# BB-Powersupply_KNX-Connection.net
KiCad netlist of a schematic drawn in EAGLE
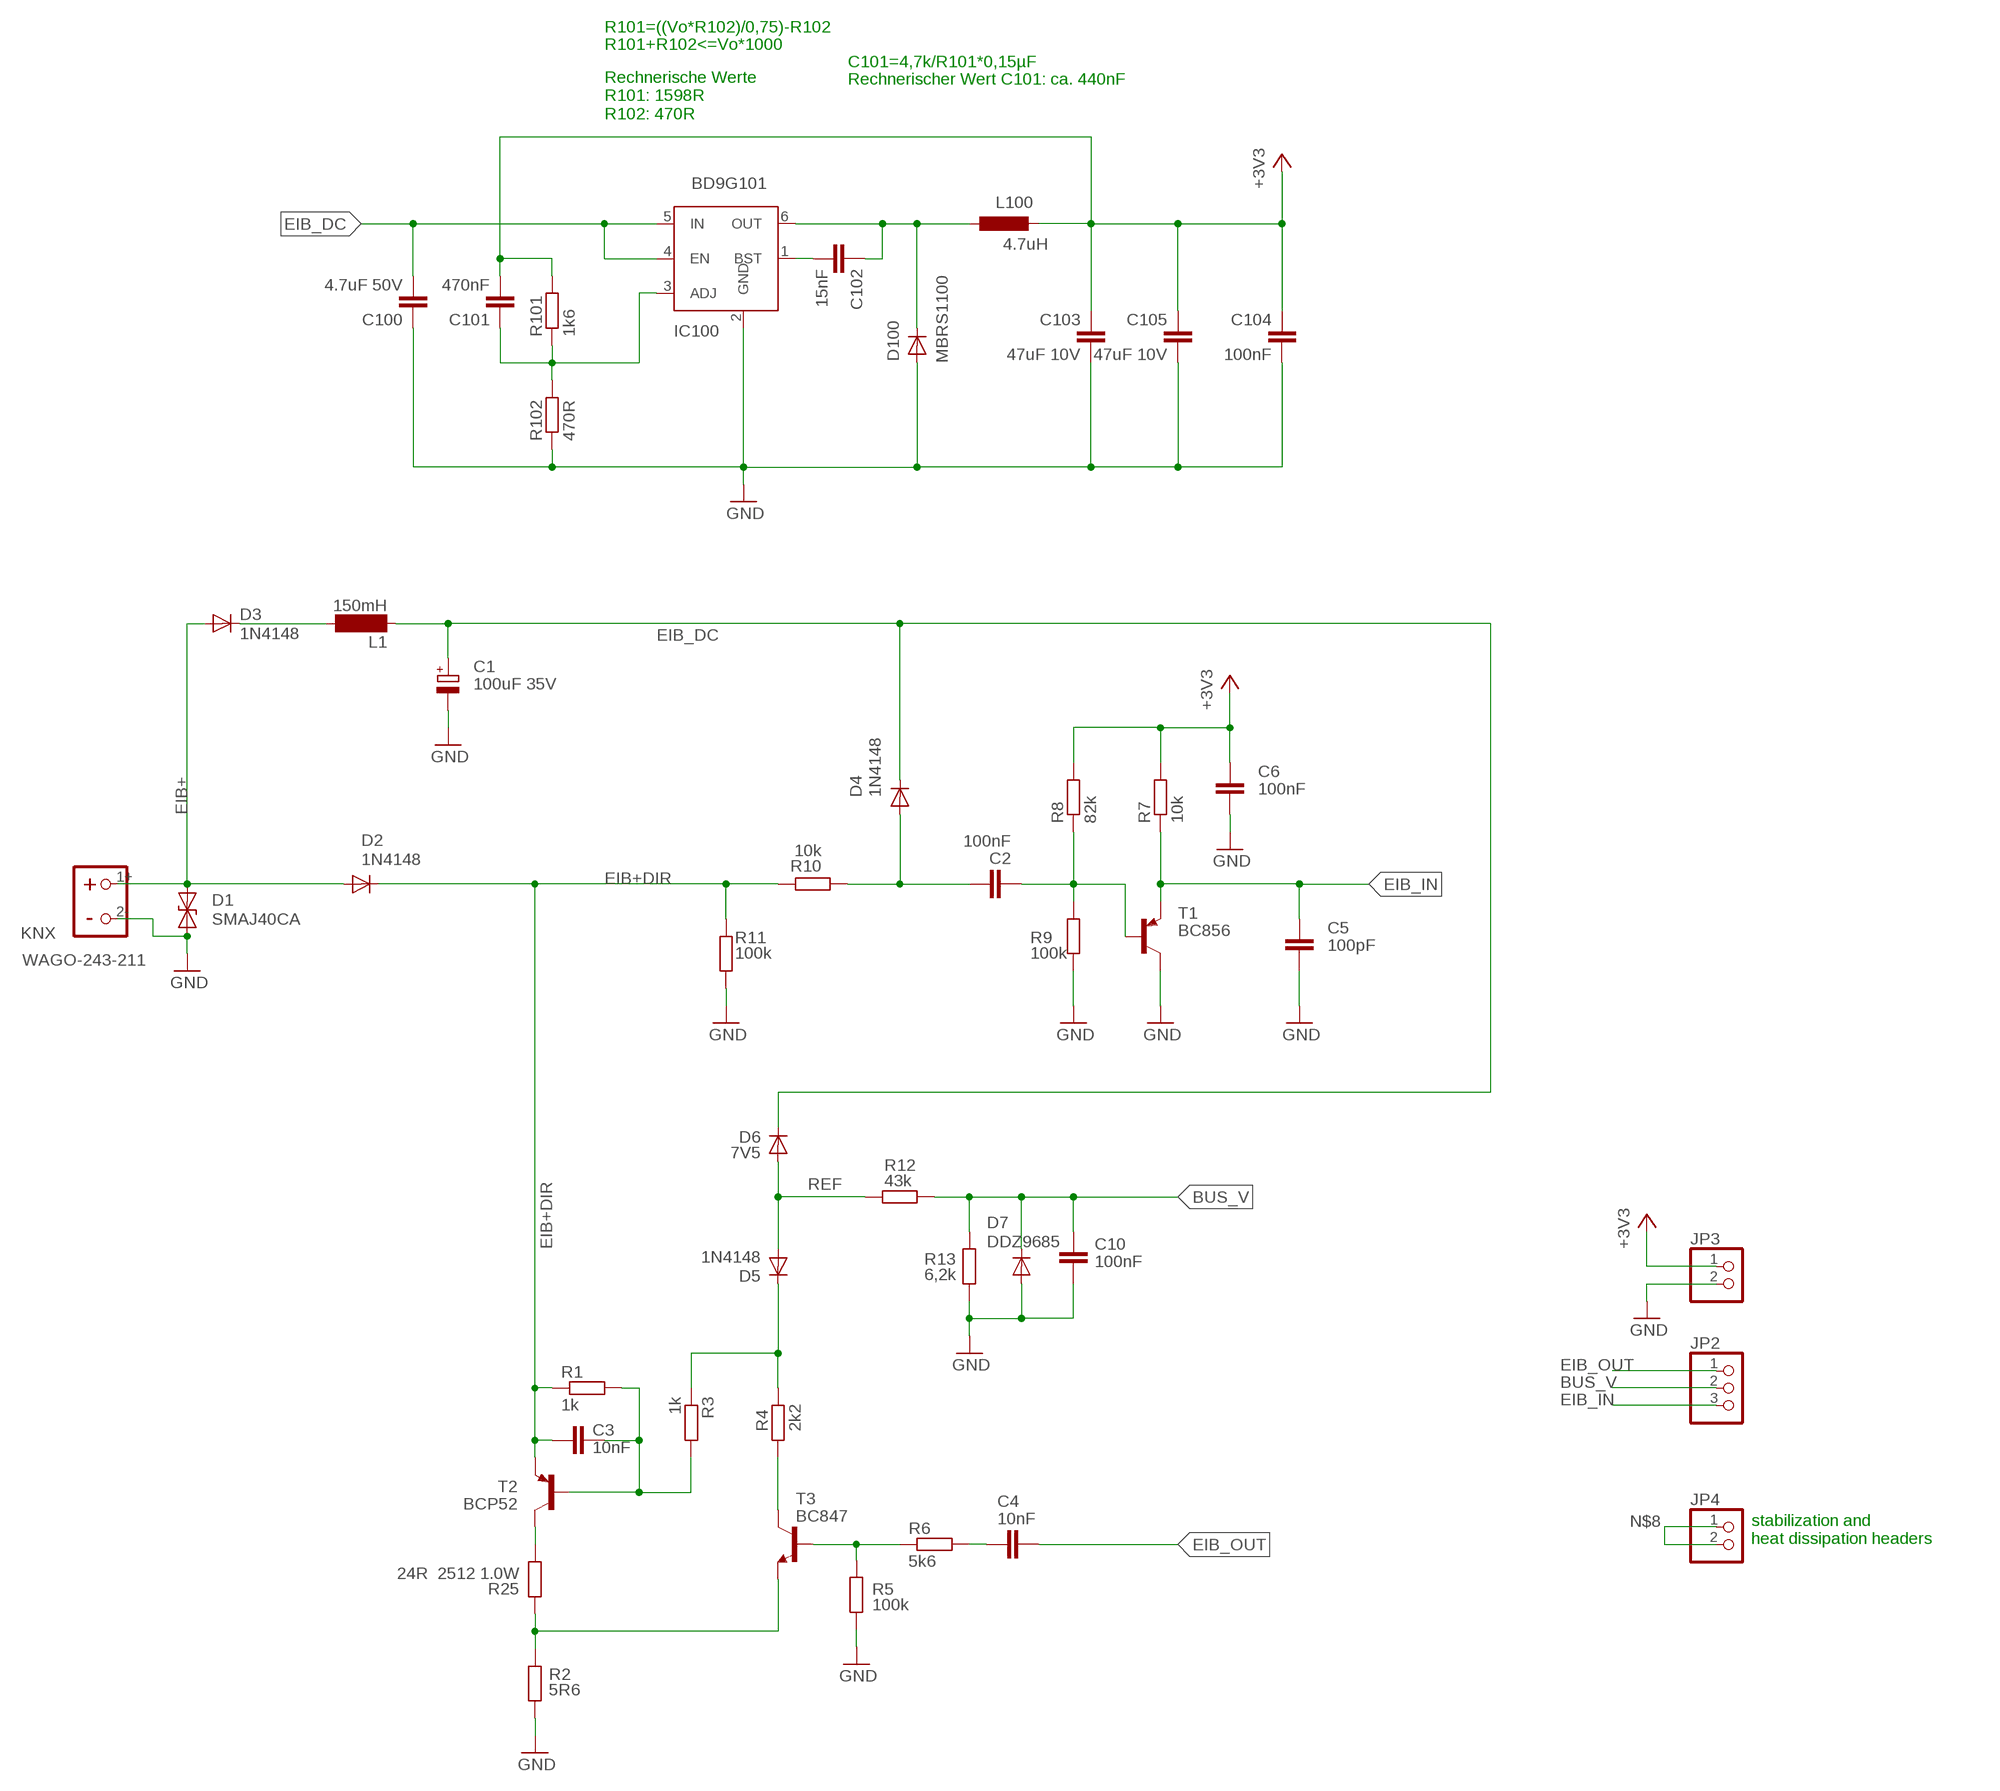
[diagram p0: schematic, sheet 1]

(export (version "E")
  (design (tool "Eeschema 10.0.6"))
  (components
    (comp (ref "C1")
      (value "100uF 35V")
      (footprint "eagle-import:SANYO-OSCON_SMD_C6")
      (libsource (lib "eagle-import") (part "CPOL-EUSANYO_SMD_C6"))
    )
    (comp (ref "C2")
      (value "100nF")
      (footprint "eagle-import:C0805")
      (libsource (lib "eagle-import") (part "C-EUC0805"))
    )
    (comp (ref "C3")
      (value "10nF")
      (footprint "eagle-import:C0805")
      (libsource (lib "eagle-import") (part "C-EUC0805"))
    )
    (comp (ref "C4")
      (value "10nF")
      (footprint "eagle-import:C0805")
      (libsource (lib "eagle-import") (part "C-EUC0805"))
    )
    (comp (ref "C5")
      (value "100pF")
      (footprint "eagle-import:C0805")
      (libsource (lib "eagle-import") (part "C-EUC0805"))
    )
    (comp (ref "C6")
      (value "100nF")
      (footprint "eagle-import:C0805")
      (libsource (lib "eagle-import") (part "C-EUC0805"))
    )
    (comp (ref "C10")
      (value "100nF")
      (footprint "eagle-import:C0805")
      (libsource (lib "eagle-import") (part "C-EUC0805"))
    )
    (comp (ref "C100")
      (value "4.7uF 50V")
      (footprint "eagle-import:C0805")
      (libsource (lib "eagle-import") (part "C-EUC0805"))
    )
    (comp (ref "C101")
      (value "470nF")
      (footprint "eagle-import:C0805")
      (libsource (lib "eagle-import") (part "C-EUC0805"))
    )
    (comp (ref "C102")
      (value "15nF")
      (footprint "eagle-import:C0805")
      (libsource (lib "eagle-import") (part "C-EUC0805"))
    )
    (comp (ref "C103")
      (value "47uF 10V")
      (footprint "eagle-import:C0805")
      (libsource (lib "eagle-import") (part "C-EUC0805"))
    )
    (comp (ref "C104")
      (value "100nF")
      (footprint "eagle-import:C0805")
      (libsource (lib "eagle-import") (part "C-EUC0805"))
    )
    (comp (ref "C105")
      (value "47uF 10V")
      (footprint "eagle-import:C0805")
      (libsource (lib "eagle-import") (part "C-EUC0805"))
    )
    (comp (ref "D1")
      (value "SMAJ40CA")
      (footprint "eagle-import:DO214AC")
      (fields (field (name "MF") "Littelfuse"))
      (libsource (lib "eagle-import") (part "SMAJCA40"))
    )
    (comp (ref "D2")
      (value "1N4148")
      (footprint "eagle-import:SOD-123")
      (libsource (lib "eagle-import") (part "DIODESOD-123"))
    )
    (comp (ref "D3")
      (value "1N4148")
      (footprint "eagle-import:SOD-123")
      (libsource (lib "eagle-import") (part "DIODESOD-123"))
    )
    (comp (ref "D4")
      (value "1N4148")
      (footprint "eagle-import:SOD-123")
      (libsource (lib "eagle-import") (part "DIODESOD-123"))
    )
    (comp (ref "D5")
      (value "1N4148")
      (footprint "eagle-import:SOD-123")
      (libsource (lib "eagle-import") (part "DIODESOD-123"))
    )
    (comp (ref "D6")
      (value "7V5")
      (footprint "eagle-import:SOD-123")
      (libsource (lib "eagle-import") (part "DIODESOD-123"))
    )
    (comp (ref "D7")
      (value "DDZ9685")
      (footprint "eagle-import:SOD-123")
      (libsource (lib "eagle-import") (part "DIODESOD-123"))
    )
    (comp (ref "D100")
      (value "MBRS1100")
      (footprint "eagle-import:SOD-123")
      (libsource (lib "eagle-import") (part "DIODESOD-123"))
    )
    (comp (ref "IC100")
      (value "BD9G101")
      (footprint "eagle-import:SOT23-6")
      (libsource (lib "eagle-import") (part "BD9G101GBD9G101G-SOT23-6"))
    )
    (comp (ref "JP2")
      (value "PINHD-1X3")
      (footprint "eagle-import:1X03")
      (libsource (lib "eagle-import") (part "PINHD-1X3"))
    )
    (comp (ref "JP3")
      (value "PINHD-1X2")
      (footprint "eagle-import:1X02")
      (libsource (lib "eagle-import") (part "PINHD-1X2"))
    )
    (comp (ref "JP4")
      (value "PINHD-1X2")
      (footprint "eagle-import:1X02")
      (libsource (lib "eagle-import") (part "PINHD-1X2"))
    )
    (comp (ref "KNX")
      (value "WAGO-243-211")
      (footprint "eagle-import:WAGO-243-211")
      (libsource (lib "eagle-import") (part "WAGO-243-211"))
    )
    (comp (ref "L1")
      (value "150mH")
      (footprint "eagle-import:BS11")
      (fields (field (name "SPICEPREFIX") "L"))
      (libsource (lib "eagle-import") (part "BS11"))
    )
    (comp (ref "L100")
      (value "4.7uH")
      (footprint "eagle-import:L4532P")
      (libsource (lib "eagle-import") (part "L-EUL4532P"))
    )
    (comp (ref "R1")
      (value "1k")
      (footprint "eagle-import:R0805")
      (libsource (lib "eagle-import") (part "R-EU_R0805"))
    )
    (comp (ref "R2")
      (value "5R6")
      (footprint "eagle-import:R0805")
      (libsource (lib "eagle-import") (part "R-EU_R0805"))
    )
    (comp (ref "R3")
      (value "1k")
      (footprint "eagle-import:R0805")
      (libsource (lib "eagle-import") (part "R-EU_R0805"))
    )
    (comp (ref "R4")
      (value "2k2")
      (footprint "eagle-import:R0805")
      (libsource (lib "eagle-import") (part "R-EU_R0805"))
    )
    (comp (ref "R5")
      (value "100k")
      (footprint "eagle-import:R0805")
      (libsource (lib "eagle-import") (part "R-EU_R0805"))
    )
    (comp (ref "R6")
      (value "5k6")
      (footprint "eagle-import:R0805")
      (libsource (lib "eagle-import") (part "R-EU_R0805"))
    )
    (comp (ref "R7")
      (value "10k")
      (footprint "eagle-import:R0805")
      (libsource (lib "eagle-import") (part "R-EU_R0805"))
    )
    (comp (ref "R8")
      (value "82k")
      (footprint "eagle-import:R0805")
      (libsource (lib "eagle-import") (part "R-EU_R0805"))
    )
    (comp (ref "R9")
      (value "100k")
      (footprint "eagle-import:R0805")
      (libsource (lib "eagle-import") (part "R-EU_R0805"))
    )
    (comp (ref "R10")
      (value "10k")
      (footprint "eagle-import:R0805")
      (libsource (lib "eagle-import") (part "R-EU_R0805"))
    )
    (comp (ref "R11")
      (value "100k")
      (footprint "eagle-import:R0805")
      (libsource (lib "eagle-import") (part "R-EU_R0805"))
    )
    (comp (ref "R12")
      (value "43k")
      (footprint "eagle-import:R0805")
      (libsource (lib "eagle-import") (part "R-EU_R0805"))
    )
    (comp (ref "R13")
      (value "6,2k")
      (footprint "eagle-import:R0805")
      (libsource (lib "eagle-import") (part "R-EU_R0805"))
    )
    (comp (ref "R25")
      (value "24R 2512 1.0W")
      (footprint "eagle-import:R2512")
      (libsource (lib "eagle-import") (part "R-EU_R2512"))
    )
    (comp (ref "R101")
      (value "1k6")
      (footprint "eagle-import:R0805")
      (libsource (lib "eagle-import") (part "R-EU_R0805"))
    )
    (comp (ref "R102")
      (value "470R")
      (footprint "eagle-import:R0805")
      (libsource (lib "eagle-import") (part "R-EU_R0805"))
    )
    (comp (ref "T1")
      (value "BC856")
      (footprint "eagle-import:SOT23-BEC")
      (libsource (lib "eagle-import") (part "BC856SMDB"))
    )
    (comp (ref "T2")
      (value "BCP52")
      (footprint "eagle-import:SOT223")
      (libsource (lib "eagle-import") (part "FZT753SMD"))
    )
    (comp (ref "T3")
      (value "BC847")
      (footprint "eagle-import:SOT23")
      (libsource (lib "eagle-import") (part "BC847"))
    )
  )
  (nets
    (net (code "1") (name "+3V3") (class "Default")
      (node (ref "C101") (pin "2") (pinfunction "2_2") (pintype "passive"))
      (node (ref "C103") (pin "1") (pinfunction "1_1") (pintype "passive"))
      (node (ref "C104") (pin "1") (pinfunction "1_1") (pintype "passive"))
      (node (ref "C105") (pin "1") (pinfunction "1_1") (pintype "passive"))
      (node (ref "C6") (pin "2") (pinfunction "2_2") (pintype "passive"))
      (node (ref "JP3") (pin "1") (pinfunction "1_1") (pintype "passive"))
      (node (ref "L100") (pin "2") (pinfunction "2_2") (pintype "passive"))
      (node (ref "R101") (pin "2") (pinfunction "2_2") (pintype "passive"))
      (node (ref "R7") (pin "2") (pinfunction "2_2") (pintype "passive"))
      (node (ref "R8") (pin "2") (pinfunction "2_2") (pintype "passive"))
    )
    (net (code "2") (name "/EIB+") (class "Default")
      (node (ref "D1") (pin "C") (pinfunction "2_C") (pintype "passive"))
      (node (ref "D2") (pin "A") (pinfunction "A_A") (pintype "passive"))
      (node (ref "D3") (pin "A") (pinfunction "A_A") (pintype "passive"))
      (node (ref "KNX") (pin "1+") (pinfunction "1+_1+") (pintype "passive"))
    )
    (net (code "3") (name "/EIB+DIR") (class "Default")
      (node (ref "C3") (pin "1") (pinfunction "1_1") (pintype "passive"))
      (node (ref "D2") (pin "C") (pinfunction "C_C") (pintype "passive"))
      (node (ref "R1") (pin "1") (pinfunction "1_1") (pintype "passive"))
      (node (ref "R10") (pin "2") (pinfunction "2_2") (pintype "passive"))
      (node (ref "R11") (pin "2") (pinfunction "2_2") (pintype "passive"))
      (node (ref "T2") (pin "3") (pinfunction "E_3") (pintype "passive"))
    )
    (net (code "4") (name "/N$8") (class "Default")
      (node (ref "JP4") (pin "1") (pinfunction "1_1") (pintype "passive"))
      (node (ref "JP4") (pin "2") (pinfunction "2_2") (pintype "passive"))
      (node (ref "R25") (pin "2") (pinfunction "2_2") (pintype "passive"))
      (node (ref "T2") (pin "2") (pinfunction "C_2") (pintype "passive"))
      (node (ref "T2") (pin "4") (pinfunction "C_4") (pintype "passive"))
    )
    (net (code "5") (name "/REF") (class "Default")
      (node (ref "D5") (pin "A") (pinfunction "A_A") (pintype "passive"))
      (node (ref "D6") (pin "A") (pinfunction "A_A") (pintype "passive"))
      (node (ref "R12") (pin "1") (pinfunction "1_1") (pintype "passive"))
    )
    (net (code "6") (name "BUS_V") (class "Default")
      (node (ref "C10") (pin "2") (pinfunction "2_2") (pintype "passive"))
      (node (ref "D7") (pin "C") (pinfunction "C_C") (pintype "passive"))
      (node (ref "JP2") (pin "2") (pinfunction "2_2") (pintype "passive"))
      (node (ref "R12") (pin "2") (pinfunction "2_2") (pintype "passive"))
      (node (ref "R13") (pin "1") (pinfunction "1_1") (pintype "passive"))
    )
    (net (code "7") (name "EIB_DC") (class "Default")
      (node (ref "C1") (pin "+") (pinfunction "+_+") (pintype "passive"))
      (node (ref "C100") (pin "2") (pinfunction "2_2") (pintype "passive"))
      (node (ref "D4") (pin "C") (pinfunction "C_C") (pintype "passive"))
      (node (ref "D6") (pin "C") (pinfunction "C_C") (pintype "passive"))
      (node (ref "IC100") (pin "4") (pinfunction "EN_4") (pintype "input"))
      (node (ref "IC100") (pin "5") (pinfunction "IN_5") (pintype "input"))
      (node (ref "L1") (pin "1") (pinfunction "1_1") (pintype "passive"))
    )
    (net (code "8") (name "EIB_IN") (class "Default")
      (node (ref "C5") (pin "2") (pinfunction "2_2") (pintype "passive"))
      (node (ref "JP2") (pin "3") (pinfunction "3_3") (pintype "passive"))
      (node (ref "R7") (pin "1") (pinfunction "1_1") (pintype "passive"))
      (node (ref "T1") (pin "E") (pinfunction "E_E") (pintype "passive"))
    )
    (net (code "9") (name "EIB_OUT") (class "Default")
      (node (ref "C4") (pin "2") (pinfunction "2_2") (pintype "passive"))
      (node (ref "JP2") (pin "1") (pinfunction "1_1") (pintype "passive"))
    )
    (net (code "10") (name "GND") (class "Default")
      (node (ref "C1") (pin "-") (pinfunction "-_-") (pintype "passive"))
      (node (ref "C10") (pin "1") (pinfunction "1_1") (pintype "passive"))
      (node (ref "C100") (pin "1") (pinfunction "1_1") (pintype "passive"))
      (node (ref "C103") (pin "2") (pinfunction "2_2") (pintype "passive"))
      (node (ref "C104") (pin "2") (pinfunction "2_2") (pintype "passive"))
      (node (ref "C105") (pin "2") (pinfunction "2_2") (pintype "passive"))
      (node (ref "C5") (pin "1") (pinfunction "1_1") (pintype "passive"))
      (node (ref "C6") (pin "1") (pinfunction "1_1") (pintype "passive"))
      (node (ref "D1") (pin "A") (pinfunction "1_A") (pintype "passive"))
      (node (ref "D100") (pin "A") (pinfunction "A_A") (pintype "passive"))
      (node (ref "D7") (pin "A") (pinfunction "A_A") (pintype "passive"))
      (node (ref "IC100") (pin "2") (pinfunction "GND_2") (pintype "power_in"))
      (node (ref "JP3") (pin "2") (pinfunction "2_2") (pintype "passive"))
      (node (ref "KNX") (pin "2-") (pinfunction "2-_2-") (pintype "passive"))
      (node (ref "R102") (pin "1") (pinfunction "1_1") (pintype "passive"))
      (node (ref "R11") (pin "1") (pinfunction "1_1") (pintype "passive"))
      (node (ref "R13") (pin "2") (pinfunction "2_2") (pintype "passive"))
      (node (ref "R2") (pin "1") (pinfunction "1_1") (pintype "passive"))
      (node (ref "R5") (pin "2") (pinfunction "2_2") (pintype "passive"))
      (node (ref "R9") (pin "1") (pinfunction "1_1") (pintype "passive"))
      (node (ref "T1") (pin "C") (pinfunction "C_C") (pintype "passive"))
    )
    (net (code "11") (name "Net-(C2-Pad1)") (class "Default")
      (node (ref "C2") (pin "1") (pinfunction "1_1") (pintype "passive"))
      (node (ref "R8") (pin "1") (pinfunction "1_1") (pintype "passive"))
      (node (ref "R9") (pin "2") (pinfunction "2_2") (pintype "passive"))
      (node (ref "T1") (pin "B") (pinfunction "B_B") (pintype "passive"))
    )
    (net (code "12") (name "Net-(C2-Pad2)") (class "Default")
      (node (ref "C2") (pin "2") (pinfunction "2_2") (pintype "passive"))
      (node (ref "D4") (pin "A") (pinfunction "A_A") (pintype "passive"))
      (node (ref "R10") (pin "1") (pinfunction "1_1") (pintype "passive"))
    )
    (net (code "13") (name "Net-(C4-Pad1)") (class "Default")
      (node (ref "C4") (pin "1") (pinfunction "1_1") (pintype "passive"))
      (node (ref "R6") (pin "2") (pinfunction "2_2") (pintype "passive"))
    )
    (net (code "14") (name "Net-(D3-PadC)") (class "Default")
      (node (ref "D3") (pin "C") (pinfunction "C_C") (pintype "passive"))
      (node (ref "L1") (pin "2") (pinfunction "2_2") (pintype "passive"))
    )
    (net (code "15") (name "Net-(D5-PadC)") (class "Default")
      (node (ref "D5") (pin "C") (pinfunction "C_C") (pintype "passive"))
      (node (ref "R3") (pin "1") (pinfunction "1_1") (pintype "passive"))
      (node (ref "R4") (pin "2") (pinfunction "2_2") (pintype "passive"))
    )
    (net (code "16") (name "Net-(IC100-ADJ)") (class "Default")
      (node (ref "C101") (pin "1") (pinfunction "1_1") (pintype "passive"))
      (node (ref "IC100") (pin "3") (pinfunction "ADJ_3") (pintype "passive"))
      (node (ref "R101") (pin "1") (pinfunction "1_1") (pintype "passive"))
      (node (ref "R102") (pin "2") (pinfunction "2_2") (pintype "passive"))
    )
    (net (code "17") (name "Net-(IC100-BST)") (class "Default")
      (node (ref "C102") (pin "2") (pinfunction "2_2") (pintype "passive"))
      (node (ref "IC100") (pin "1") (pinfunction "BST_1") (pintype "output"))
    )
    (net (code "18") (name "Net-(IC100-OUT)") (class "Default")
      (node (ref "C102") (pin "1") (pinfunction "1_1") (pintype "passive"))
      (node (ref "D100") (pin "C") (pinfunction "C_C") (pintype "passive"))
      (node (ref "IC100") (pin "6") (pinfunction "OUT_6") (pintype "output"))
      (node (ref "L100") (pin "1") (pinfunction "1_1") (pintype "passive"))
    )
    (net (code "19") (name "Net-(T2-B)") (class "Default")
      (node (ref "C3") (pin "2") (pinfunction "2_2") (pintype "passive"))
      (node (ref "R1") (pin "2") (pinfunction "2_2") (pintype "passive"))
      (node (ref "R3") (pin "2") (pinfunction "2_2") (pintype "passive"))
      (node (ref "T2") (pin "1") (pinfunction "B_1") (pintype "passive"))
    )
    (net (code "20") (name "Net-(T3-B)") (class "Default")
      (node (ref "R5") (pin "1") (pinfunction "1_1") (pintype "passive"))
      (node (ref "R6") (pin "1") (pinfunction "1_1") (pintype "passive"))
      (node (ref "T3") (pin "1") (pinfunction "B_1") (pintype "passive"))
    )
    (net (code "21") (name "Net-(T3-C)") (class "Default")
      (node (ref "R4") (pin "1") (pinfunction "1_1") (pintype "passive"))
      (node (ref "T3") (pin "3") (pinfunction "C_3") (pintype "passive"))
    )
    (net (code "22") (name "Net-(T3-E)") (class "Default")
      (node (ref "R2") (pin "2") (pinfunction "2_2") (pintype "passive"))
      (node (ref "R25") (pin "1") (pinfunction "1_1") (pintype "passive"))
      (node (ref "T3") (pin "2") (pinfunction "E_2") (pintype "passive"))
    )
  )
)
